# 03_LED7SEG.net
KiCad netlist of a schematic drawn in Altium Designer
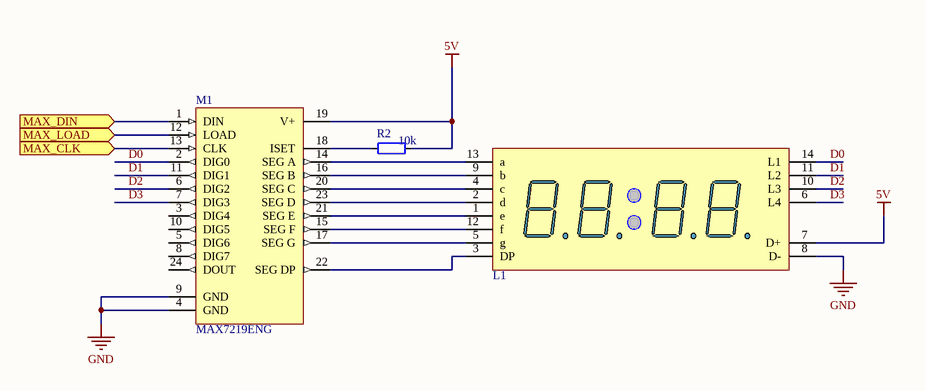
[diagram p0: [03] LED7SEG.SchDoc]

(export (version "E")
  (design (tool "Eeschema 10.0.6"))
  (components
    (comp (ref "L1")
      (value "Led 7 Seg 4 digit - Anode")
      (footprint "LED7SEG-4-0.56-RG")
      (libsource (lib "My Library") (part "LED7SEG-4-RG"))
    )
    (comp (ref "M1")
      (value "MAX7219ENG")
      (footprint "SO24")
      (description "Serially Interfaced, 8-Digit LED Display Driver")
      (fields (field (name "PUBLISHER") "Altium Limited"))
      (libsource (lib "My Library") (part "MAX7219ENG"))
    )
    (comp (ref "R2")
      (value "10k")
      (footprint "RES-SMD-0805")
      (description "Resistor")
      (fields
        (field (name "MANUFACTURER") "Generic Components")
        (field (name "PUBLISHER") "Altium Hobart Technology Centre")
      )
      (libsource (lib "My Library") (part "Resistor - SMD"))
    )
  )
  (nets
    (net (code "1") (name "/D0") (class "Default")
      (node (ref "L1") (pin "14") (pinfunction "L1_14") (pintype "passive"))
      (node (ref "M1") (pin "2") (pinfunction "DIG0_2") (pintype "output"))
    )
    (net (code "2") (name "/D1") (class "Default")
      (node (ref "L1") (pin "11") (pinfunction "L2_11") (pintype "passive"))
      (node (ref "M1") (pin "11") (pinfunction "DIG1_11") (pintype "output"))
    )
    (net (code "3") (name "/D2") (class "Default")
      (node (ref "L1") (pin "10") (pinfunction "L3_10") (pintype "passive"))
      (node (ref "M1") (pin "6") (pinfunction "DIG2_6") (pintype "output"))
    )
    (net (code "4") (name "/D3") (class "Default")
      (node (ref "L1") (pin "6") (pinfunction "L4_6") (pintype "passive"))
      (node (ref "M1") (pin "7") (pinfunction "DIG3_7") (pintype "output"))
    )
    (net (code "5") (name "/MAX_CLK") (class "Default")
      (node (ref "M1") (pin "13") (pinfunction "CLK_13") (pintype "input"))
    )
    (net (code "6") (name "/MAX_DIN") (class "Default")
      (node (ref "M1") (pin "1") (pinfunction "DIN_1") (pintype "input"))
    )
    (net (code "7") (name "/MAX_LOAD") (class "Default")
      (node (ref "M1") (pin "12") (pinfunction "LOAD_12") (pintype "input"))
    )
    (net (code "8") (name "5V") (class "Default")
      (node (ref "L1") (pin "7") (pinfunction "D+_7") (pintype "passive"))
      (node (ref "M1") (pin "19") (pinfunction "V+_19") (pintype "power_in"))
      (node (ref "R2") (pin "2") (pinfunction "2_2") (pintype "passive"))
    )
    (net (code "9") (name "GND") (class "Default")
      (node (ref "L1") (pin "8") (pinfunction "D-_8") (pintype "passive"))
      (node (ref "M1") (pin "4") (pinfunction "GND_4") (pintype "power_in"))
      (node (ref "M1") (pin "9") (pinfunction "GND_9") (pintype "power_in"))
    )
    (net (code "10") (name "Net-(L1-DP)") (class "Default")
      (node (ref "L1") (pin "3") (pinfunction "DP_3") (pintype "passive"))
      (node (ref "M1") (pin "22") (pinfunction "SEG_DP_22") (pintype "output"))
    )
    (net (code "11") (name "Net-(L1-a)") (class "Default")
      (node (ref "L1") (pin "13") (pinfunction "a_13") (pintype "passive"))
      (node (ref "M1") (pin "14") (pinfunction "SEG_A_14") (pintype "output"))
    )
    (net (code "12") (name "Net-(L1-b)") (class "Default")
      (node (ref "L1") (pin "9") (pinfunction "b_9") (pintype "passive"))
      (node (ref "M1") (pin "16") (pinfunction "SEG_B_16") (pintype "output"))
    )
    (net (code "13") (name "Net-(L1-c)") (class "Default")
      (node (ref "L1") (pin "4") (pinfunction "c_4") (pintype "passive"))
      (node (ref "M1") (pin "20") (pinfunction "SEG_C_20") (pintype "output"))
    )
    (net (code "14") (name "Net-(L1-d)") (class "Default")
      (node (ref "L1") (pin "2") (pinfunction "d_2") (pintype "passive"))
      (node (ref "M1") (pin "23") (pinfunction "SEG_D_23") (pintype "output"))
    )
    (net (code "15") (name "Net-(L1-e)") (class "Default")
      (node (ref "L1") (pin "1") (pinfunction "e_1") (pintype "passive"))
      (node (ref "M1") (pin "21") (pinfunction "SEG_E_21") (pintype "output"))
    )
    (net (code "16") (name "Net-(L1-f)") (class "Default")
      (node (ref "L1") (pin "12") (pinfunction "f_12") (pintype "passive"))
      (node (ref "M1") (pin "15") (pinfunction "SEG_F_15") (pintype "output"))
    )
    (net (code "17") (name "Net-(L1-g)") (class "Default")
      (node (ref "L1") (pin "5") (pinfunction "g_5") (pintype "passive"))
      (node (ref "M1") (pin "17") (pinfunction "SEG_G_17") (pintype "output"))
    )
    (net (code "18") (name "Net-(M1-ISET)") (class "Default")
      (node (ref "M1") (pin "18") (pinfunction "ISET_18") (pintype "passive"))
      (node (ref "R2") (pin "1") (pinfunction "1_1") (pintype "passive"))
    )
    (net (code "19") (name "unconnected-(M1-DIG4-Pad3)") (class "Default")
      (node (ref "M1") (pin "3") (pinfunction "DIG4_3") (pintype "output"))
    )
    (net (code "20") (name "unconnected-(M1-DIG5-Pad10)") (class "Default")
      (node (ref "M1") (pin "10") (pinfunction "DIG5_10") (pintype "output"))
    )
    (net (code "21") (name "unconnected-(M1-DIG6-Pad5)") (class "Default")
      (node (ref "M1") (pin "5") (pinfunction "DIG6_5") (pintype "output"))
    )
    (net (code "22") (name "unconnected-(M1-DIG7-Pad8)") (class "Default")
      (node (ref "M1") (pin "8") (pinfunction "DIG7_8") (pintype "output"))
    )
    (net (code "23") (name "unconnected-(M1-DOUT-Pad24)") (class "Default")
      (node (ref "M1") (pin "24") (pinfunction "DOUT_24") (pintype "output"))
    )
  )
)
